# ATtiny.net
KiCad netlist of a schematic drawn in Altium Designer
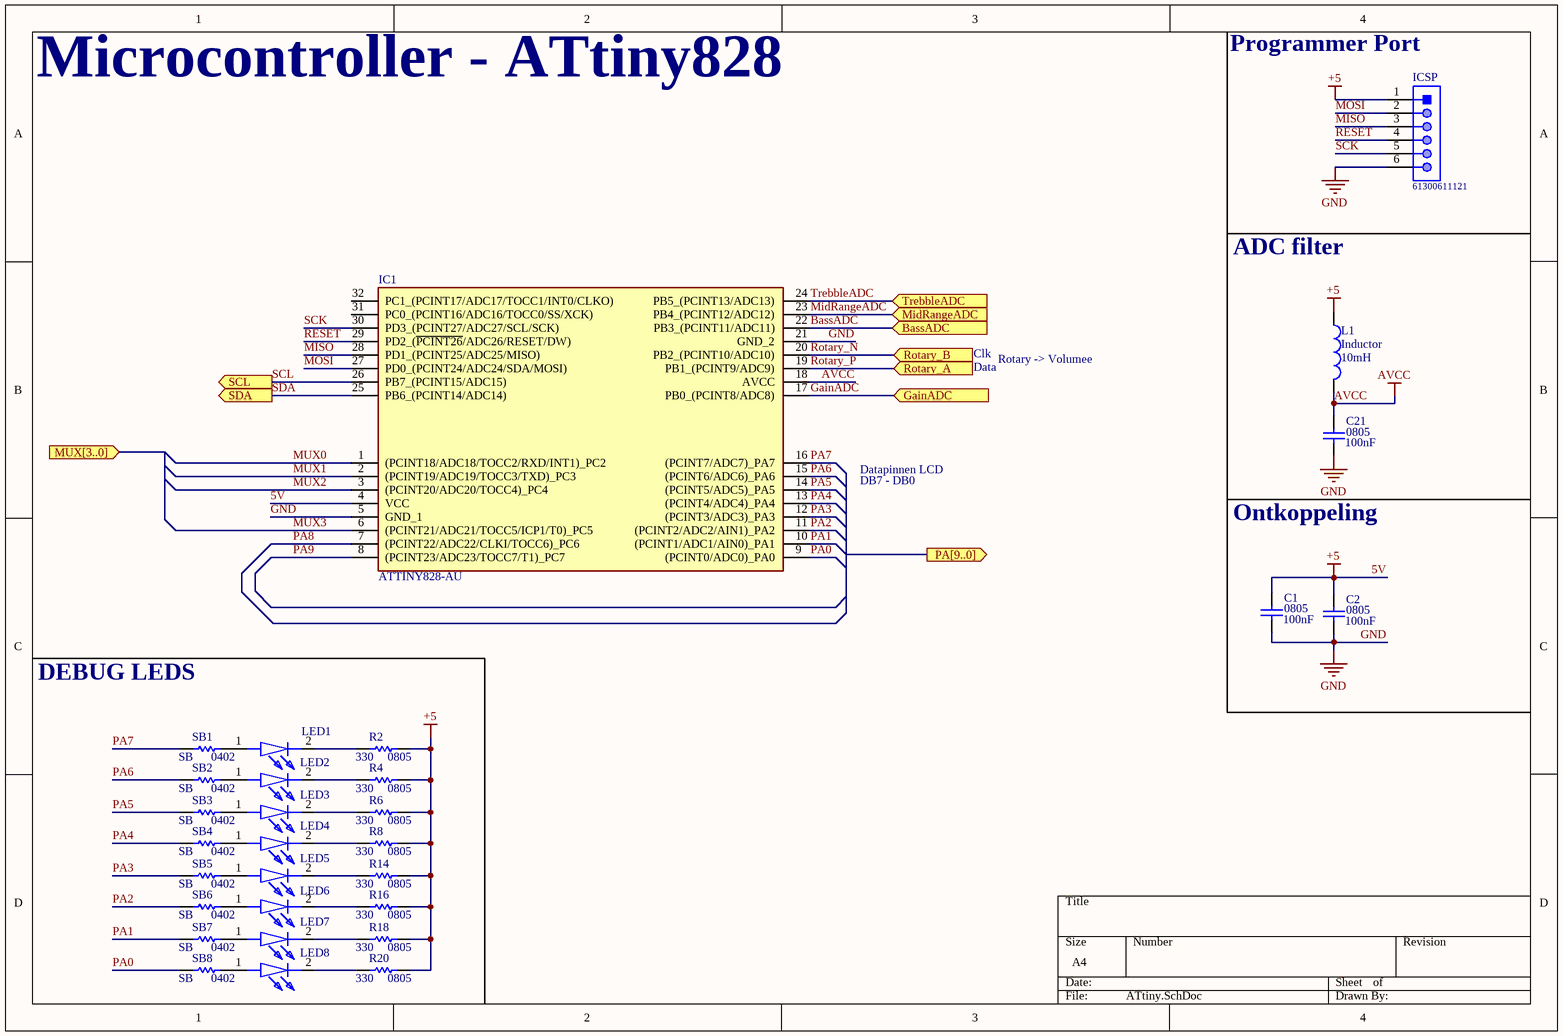
[diagram p0: ATtiny.SchDoc]

(export (version "E")
  (design (tool "Eeschema 10.0.6"))
  (components
    (comp (ref "C1")
      (value "0805")
      (footprint "6-0805_N")
      (description "Capacitor")
      (fields (field (name "ALTIUM_VALUE") "100nF") (field (name "PUBLISHER") "Altium Limited"))
      (libsource (lib "Miscellaneous Devices") (part "Cap"))
    )
    (comp (ref "C2")
      (value "0805")
      (footprint "6-0805_N")
      (description "Capacitor")
      (fields (field (name "ALTIUM_VALUE") "100nF") (field (name "PUBLISHER") "Altium Limited"))
      (libsource (lib "Miscellaneous Devices") (part "Cap"))
    )
    (comp (ref "C21")
      (value "0805")
      (footprint "6-0805_N")
      (description "Capacitor")
      (fields (field (name "ALTIUM_VALUE") "100nF") (field (name "PUBLISHER") "Altium Limited"))
      (libsource (lib "Miscellaneous Devices") (part "Cap"))
    )
    (comp (ref "IC1")
      (value "ATTINY828-AU")
      (footprint "SamacSys:QFP80P900X900X120-32N")
      (description "Integrated Circuit")
      (libsource (lib "SamacSys") (part "ATTINY828-AU"))
    )
    (comp (ref "ICSP")
      (value "61300611121")
      (footprint "61300611121")
      (description "THT Vertical Pin Header WR-PHD, Pitch 2.54 mm, Single Row, 6 pins")
      (fields (field (name "MANUFACTURER") "Wurth Elektronik") (field (name "PUBLISHER") "WurthElektronik"))
      (libsource (lib "Altium Content Vault") (part "WE-CN-1P-M-R6"))
    )
    (comp (ref "L1")
      (value "Inductor")
      (footprint "2220")
      (fields (field (name "ALTIUM_VALUE") "10mH") (field (name "PUBLISHER") "Altium Limited"))
      (libsource (lib "Miscellaneous Devices") (part "Inductor"))
    )
    (comp (ref "LED1")
      (value "ELM70303GD")
      (footprint "SamacSys:ELM70303GD")
      (description "LED")
      (fields (field (name "MOUSER PART NUMBER") "749-ELM70303GD"))
      (libsource (lib "SamacSys") (part "ELM70303GD"))
    )
    (comp (ref "LED2")
      (value "ELM70303GD")
      (footprint "SamacSys:ELM70303GD")
      (description "LED")
      (fields (field (name "MOUSER PART NUMBER") "749-ELM70303GD"))
      (libsource (lib "SamacSys") (part "ELM70303GD"))
    )
    (comp (ref "LED3")
      (value "ELM70303GD")
      (footprint "SamacSys:ELM70303GD")
      (description "LED")
      (fields (field (name "MOUSER PART NUMBER") "749-ELM70303GD"))
      (libsource (lib "SamacSys") (part "ELM70303GD"))
    )
    (comp (ref "LED4")
      (value "ELM70303GD")
      (footprint "SamacSys:ELM70303GD")
      (description "LED")
      (fields (field (name "MOUSER PART NUMBER") "749-ELM70303GD"))
      (libsource (lib "SamacSys") (part "ELM70303GD"))
    )
    (comp (ref "LED5")
      (value "ELM70303GD")
      (footprint "SamacSys:ELM70303GD")
      (description "LED")
      (fields (field (name "MOUSER PART NUMBER") "749-ELM70303GD"))
      (libsource (lib "SamacSys") (part "ELM70303GD"))
    )
    (comp (ref "LED6")
      (value "ELM70303GD")
      (footprint "SamacSys:ELM70303GD")
      (description "LED")
      (fields (field (name "MOUSER PART NUMBER") "749-ELM70303GD"))
      (libsource (lib "SamacSys") (part "ELM70303GD"))
    )
    (comp (ref "LED7")
      (value "ELM70303GD")
      (footprint "SamacSys:ELM70303GD")
      (description "LED")
      (fields (field (name "MOUSER PART NUMBER") "749-ELM70303GD"))
      (libsource (lib "SamacSys") (part "ELM70303GD"))
    )
    (comp (ref "LED8")
      (value "ELM70303GD")
      (footprint "SamacSys:ELM70303GD")
      (description "LED")
      (fields (field (name "MOUSER PART NUMBER") "749-ELM70303GD"))
      (libsource (lib "SamacSys") (part "ELM70303GD"))
    )
    (comp (ref "R2")
      (value "0805")
      (footprint "6-0805_N")
      (description "Resistor")
      (fields (field (name "ALTIUM_VALUE") "330") (field (name "PUBLISHER") "Altium Limited"))
      (libsource (lib "Miscellaneous Devices") (part "Res1"))
    )
    (comp (ref "R4")
      (value "0805")
      (footprint "6-0805_N")
      (description "Resistor")
      (fields (field (name "ALTIUM_VALUE") "330") (field (name "PUBLISHER") "Altium Limited"))
      (libsource (lib "Miscellaneous Devices") (part "Res1"))
    )
    (comp (ref "R6")
      (value "0805")
      (footprint "6-0805_N")
      (description "Resistor")
      (fields (field (name "ALTIUM_VALUE") "330") (field (name "PUBLISHER") "Altium Limited"))
      (libsource (lib "Miscellaneous Devices") (part "Res1"))
    )
    (comp (ref "R8")
      (value "0805")
      (footprint "6-0805_N")
      (description "Resistor")
      (fields (field (name "ALTIUM_VALUE") "330") (field (name "PUBLISHER") "Altium Limited"))
      (libsource (lib "Miscellaneous Devices") (part "Res1"))
    )
    (comp (ref "R14")
      (value "0805")
      (footprint "6-0805_N")
      (description "Resistor")
      (fields (field (name "ALTIUM_VALUE") "330") (field (name "PUBLISHER") "Altium Limited"))
      (libsource (lib "Miscellaneous Devices") (part "Res1"))
    )
    (comp (ref "R16")
      (value "0805")
      (footprint "6-0805_N")
      (description "Resistor")
      (fields (field (name "ALTIUM_VALUE") "330") (field (name "PUBLISHER") "Altium Limited"))
      (libsource (lib "Miscellaneous Devices") (part "Res1"))
    )
    (comp (ref "R18")
      (value "0805")
      (footprint "6-0805_N")
      (description "Resistor")
      (fields (field (name "ALTIUM_VALUE") "330") (field (name "PUBLISHER") "Altium Limited"))
      (libsource (lib "Miscellaneous Devices") (part "Res1"))
    )
    (comp (ref "R20")
      (value "0805")
      (footprint "6-0805_N")
      (description "Resistor")
      (fields (field (name "ALTIUM_VALUE") "330") (field (name "PUBLISHER") "Altium Limited"))
      (libsource (lib "Miscellaneous Devices") (part "Res1"))
    )
    (comp (ref "SB1")
      (value "0402")
      (footprint "0402")
      (description "Resistor")
      (fields (field (name "ALTIUM_VALUE") "SB") (field (name "PUBLISHER") "Altium Limited"))
      (libsource (lib "Miscellaneous Devices") (part "Res1"))
    )
    (comp (ref "SB2")
      (value "0402")
      (footprint "0402")
      (description "Resistor")
      (fields (field (name "ALTIUM_VALUE") "SB") (field (name "PUBLISHER") "Altium Limited"))
      (libsource (lib "Miscellaneous Devices") (part "Res1"))
    )
    (comp (ref "SB3")
      (value "0402")
      (footprint "0402")
      (description "Resistor")
      (fields (field (name "ALTIUM_VALUE") "SB") (field (name "PUBLISHER") "Altium Limited"))
      (libsource (lib "Miscellaneous Devices") (part "Res1"))
    )
    (comp (ref "SB4")
      (value "0402")
      (footprint "0402")
      (description "Resistor")
      (fields (field (name "ALTIUM_VALUE") "SB") (field (name "PUBLISHER") "Altium Limited"))
      (libsource (lib "Miscellaneous Devices") (part "Res1"))
    )
    (comp (ref "SB5")
      (value "0402")
      (footprint "0402")
      (description "Resistor")
      (fields (field (name "ALTIUM_VALUE") "SB") (field (name "PUBLISHER") "Altium Limited"))
      (libsource (lib "Miscellaneous Devices") (part "Res1"))
    )
    (comp (ref "SB6")
      (value "0402")
      (footprint "0402")
      (description "Resistor")
      (fields (field (name "ALTIUM_VALUE") "SB") (field (name "PUBLISHER") "Altium Limited"))
      (libsource (lib "Miscellaneous Devices") (part "Res1"))
    )
    (comp (ref "SB7")
      (value "0402")
      (footprint "0402")
      (description "Resistor")
      (fields (field (name "ALTIUM_VALUE") "SB") (field (name "PUBLISHER") "Altium Limited"))
      (libsource (lib "Miscellaneous Devices") (part "Res1"))
    )
    (comp (ref "SB8")
      (value "0402")
      (footprint "0402")
      (description "Resistor")
      (fields (field (name "ALTIUM_VALUE") "SB") (field (name "PUBLISHER") "Altium Limited"))
      (libsource (lib "Miscellaneous Devices") (part "Res1"))
    )
  )
  (nets
    (net (code "1") (name "+5") (class "Default")
      (node (ref "C1") (pin "1") (pinfunction "1_1") (pintype "passive"))
      (node (ref "C2") (pin "1") (pinfunction "1_1") (pintype "passive"))
      (node (ref "IC1") (pin "4") (pinfunction "VCC_4") (pintype "passive"))
      (node (ref "ICSP") (pin "1") (pinfunction "1_1") (pintype "passive"))
      (node (ref "L1") (pin "1") (pinfunction "1_1") (pintype "passive"))
      (node (ref "R14") (pin "1") (pinfunction "1_1") (pintype "passive"))
      (node (ref "R16") (pin "1") (pinfunction "1_1") (pintype "passive"))
      (node (ref "R18") (pin "1") (pinfunction "1_1") (pintype "passive"))
      (node (ref "R2") (pin "1") (pinfunction "1_1") (pintype "passive"))
      (node (ref "R20") (pin "1") (pinfunction "1_1") (pintype "passive"))
      (node (ref "R4") (pin "1") (pinfunction "1_1") (pintype "passive"))
      (node (ref "R6") (pin "1") (pinfunction "1_1") (pintype "passive"))
      (node (ref "R8") (pin "1") (pinfunction "1_1") (pintype "passive"))
    )
    (net (code "2") (name "/BassADC") (class "Default")
      (node (ref "IC1") (pin "22") (pinfunction "PB3_(PCINT11/ADC11)_22") (pintype "passive"))
    )
    (net (code "3") (name "/GainADC") (class "Default")
      (node (ref "IC1") (pin "17") (pinfunction "PB0_(PCINT8/ADC8)_17") (pintype "passive"))
    )
    (net (code "4") (name "/MISO") (class "Default")
      (node (ref "IC1") (pin "28") (pinfunction "PD1_(PCINT25/ADC25/MISO)_28") (pintype "passive"))
      (node (ref "ICSP") (pin "3") (pinfunction "3_3") (pintype "passive"))
    )
    (net (code "5") (name "/MOSI") (class "Default")
      (node (ref "IC1") (pin "27") (pinfunction "PD0_(PCINT24/ADC24/SDA/MOSI)_27") (pintype "passive"))
      (node (ref "ICSP") (pin "2") (pinfunction "2_2") (pintype "passive"))
    )
    (net (code "6") (name "/MUX0") (class "Default")
      (node (ref "IC1") (pin "1") (pinfunction "(PCINT18/ADC18/TOCC2/RXD/INT1)_PC2_1") (pintype "passive"))
    )
    (net (code "7") (name "/MUX1") (class "Default")
      (node (ref "IC1") (pin "2") (pinfunction "(PCINT19/ADC19/TOCC3/TXD)_PC3_2") (pintype "passive"))
    )
    (net (code "8") (name "/MUX2") (class "Default")
      (node (ref "IC1") (pin "3") (pinfunction "(PCINT20/ADC20/TOCC4)_PC4_3") (pintype "passive"))
    )
    (net (code "9") (name "/MUX3") (class "Default")
      (node (ref "IC1") (pin "6") (pinfunction "(PCINT21/ADC21/TOCC5/ICP1/T0)_PC5_6") (pintype "passive"))
    )
    (net (code "11") (name "/MidRangeADC") (class "Default")
      (node (ref "IC1") (pin "23") (pinfunction "PB4_(PCINT12/ADC12)_23") (pintype "passive"))
    )
    (net (code "12") (name "/PA0") (class "Default")
      (node (ref "IC1") (pin "9") (pinfunction "(PCINT0/ADC0)_PA0_9") (pintype "passive"))
      (node (ref "SB8") (pin "2") (pinfunction "2_2") (pintype "passive"))
    )
    (net (code "13") (name "/PA1") (class "Default")
      (node (ref "IC1") (pin "10") (pinfunction "(PCINT1/ADC1/AIN0)_PA1_10") (pintype "passive"))
      (node (ref "SB7") (pin "2") (pinfunction "2_2") (pintype "passive"))
    )
    (net (code "14") (name "/PA2") (class "Default")
      (node (ref "IC1") (pin "11") (pinfunction "(PCINT2/ADC2/AIN1)_PA2_11") (pintype "passive"))
      (node (ref "SB6") (pin "2") (pinfunction "2_2") (pintype "passive"))
    )
    (net (code "15") (name "/PA3") (class "Default")
      (node (ref "IC1") (pin "12") (pinfunction "(PCINT3/ADC3)_PA3_12") (pintype "passive"))
      (node (ref "SB5") (pin "2") (pinfunction "2_2") (pintype "passive"))
    )
    (net (code "16") (name "/PA4") (class "Default")
      (node (ref "IC1") (pin "13") (pinfunction "(PCINT4/ADC4)_PA4_13") (pintype "passive"))
      (node (ref "SB4") (pin "2") (pinfunction "2_2") (pintype "passive"))
    )
    (net (code "17") (name "/PA5") (class "Default")
      (node (ref "IC1") (pin "14") (pinfunction "(PCINT5/ADC5)_PA5_14") (pintype "passive"))
      (node (ref "SB3") (pin "2") (pinfunction "2_2") (pintype "passive"))
    )
    (net (code "18") (name "/PA6") (class "Default")
      (node (ref "IC1") (pin "15") (pinfunction "(PCINT6/ADC6)_PA6_15") (pintype "passive"))
      (node (ref "SB2") (pin "2") (pinfunction "2_2") (pintype "passive"))
    )
    (net (code "19") (name "/PA7") (class "Default")
      (node (ref "IC1") (pin "16") (pinfunction "(PCINT7/ADC7)_PA7_16") (pintype "passive"))
      (node (ref "SB1") (pin "2") (pinfunction "2_2") (pintype "passive"))
    )
    (net (code "20") (name "/PA8") (class "Default")
      (node (ref "IC1") (pin "7") (pinfunction "(PCINT22/ADC22/CLKI/TOCC6)_PC6_7") (pintype "passive"))
    )
    (net (code "21") (name "/PA9") (class "Default")
      (node (ref "IC1") (pin "8") (pinfunction "(PCINT23/ADC23/TOCC7/T1)_PC7_8") (pintype "passive"))
    )
    (net (code "23") (name "/RESET") (class "Default")
      (node (ref "IC1") (pin "29") (pinfunction "PD2_(~{PCINT26}/ADC26/RESET/DW)_29") (pintype "passive"))
      (node (ref "ICSP") (pin "4") (pinfunction "4_4") (pintype "passive"))
    )
    (net (code "24") (name "/Rotary_N") (class "Default")
      (node (ref "IC1") (pin "20") (pinfunction "PB2_(PCINT10/ADC10)_20") (pintype "passive"))
    )
    (net (code "25") (name "/Rotary_P") (class "Default")
      (node (ref "IC1") (pin "19") (pinfunction "PB1_(PCINT9/ADC9)_19") (pintype "passive"))
    )
    (net (code "26") (name "/SCK") (class "Default")
      (node (ref "IC1") (pin "30") (pinfunction "PD3_(PCINT27/ADC27/SCL/SCK)_30") (pintype "passive"))
      (node (ref "ICSP") (pin "5") (pinfunction "5_5") (pintype "passive"))
    )
    (net (code "27") (name "/SCL") (class "Default")
      (node (ref "IC1") (pin "26") (pinfunction "PB7_(PCINT15/ADC15)_26") (pintype "passive"))
    )
    (net (code "28") (name "/SDA") (class "Default")
      (node (ref "IC1") (pin "25") (pinfunction "PB6_(PCINT14/ADC14)_25") (pintype "passive"))
    )
    (net (code "29") (name "/TrebbleADC") (class "Default")
      (node (ref "IC1") (pin "24") (pinfunction "PB5_(PCINT13/ADC13)_24") (pintype "passive"))
    )
    (net (code "30") (name "AVCC") (class "Default")
      (node (ref "C21") (pin "1") (pinfunction "1_1") (pintype "passive"))
      (node (ref "IC1") (pin "18") (pinfunction "AVCC_18") (pintype "passive"))
      (node (ref "L1") (pin "2") (pinfunction "2_2") (pintype "passive"))
    )
    (net (code "31") (name "GND") (class "Default")
      (node (ref "C1") (pin "2") (pinfunction "2_2") (pintype "passive"))
      (node (ref "C2") (pin "2") (pinfunction "2_2") (pintype "passive"))
      (node (ref "C21") (pin "2") (pinfunction "2_2") (pintype "passive"))
      (node (ref "IC1") (pin "21") (pinfunction "GND_2_21") (pintype "passive"))
      (node (ref "IC1") (pin "5") (pinfunction "GND_1_5") (pintype "passive"))
      (node (ref "ICSP") (pin "6") (pinfunction "6_6") (pintype "passive"))
    )
    (net (code "32") (name "Net-(LED1-A)") (class "Default")
      (node (ref "LED1") (pin "1") (pinfunction "A_1") (pintype "passive"))
      (node (ref "SB1") (pin "1") (pinfunction "1_1") (pintype "passive"))
    )
    (net (code "33") (name "Net-(LED1-K)") (class "Default")
      (node (ref "LED1") (pin "2") (pinfunction "K_2") (pintype "passive"))
      (node (ref "R2") (pin "2") (pinfunction "2_2") (pintype "passive"))
    )
    (net (code "34") (name "Net-(LED2-A)") (class "Default")
      (node (ref "LED2") (pin "1") (pinfunction "A_1") (pintype "passive"))
      (node (ref "SB2") (pin "1") (pinfunction "1_1") (pintype "passive"))
    )
    (net (code "35") (name "Net-(LED2-K)") (class "Default")
      (node (ref "LED2") (pin "2") (pinfunction "K_2") (pintype "passive"))
      (node (ref "R4") (pin "2") (pinfunction "2_2") (pintype "passive"))
    )
    (net (code "36") (name "Net-(LED3-A)") (class "Default")
      (node (ref "LED3") (pin "1") (pinfunction "A_1") (pintype "passive"))
      (node (ref "SB3") (pin "1") (pinfunction "1_1") (pintype "passive"))
    )
    (net (code "37") (name "Net-(LED3-K)") (class "Default")
      (node (ref "LED3") (pin "2") (pinfunction "K_2") (pintype "passive"))
      (node (ref "R6") (pin "2") (pinfunction "2_2") (pintype "passive"))
    )
    (net (code "38") (name "Net-(LED4-A)") (class "Default")
      (node (ref "LED4") (pin "1") (pinfunction "A_1") (pintype "passive"))
      (node (ref "SB4") (pin "1") (pinfunction "1_1") (pintype "passive"))
    )
    (net (code "39") (name "Net-(LED4-K)") (class "Default")
      (node (ref "LED4") (pin "2") (pinfunction "K_2") (pintype "passive"))
      (node (ref "R8") (pin "2") (pinfunction "2_2") (pintype "passive"))
    )
    (net (code "40") (name "Net-(LED5-A)") (class "Default")
      (node (ref "LED5") (pin "1") (pinfunction "A_1") (pintype "passive"))
      (node (ref "SB5") (pin "1") (pinfunction "1_1") (pintype "passive"))
    )
    (net (code "41") (name "Net-(LED5-K)") (class "Default")
      (node (ref "LED5") (pin "2") (pinfunction "K_2") (pintype "passive"))
      (node (ref "R14") (pin "2") (pinfunction "2_2") (pintype "passive"))
    )
    (net (code "42") (name "Net-(LED6-A)") (class "Default")
      (node (ref "LED6") (pin "1") (pinfunction "A_1") (pintype "passive"))
      (node (ref "SB6") (pin "1") (pinfunction "1_1") (pintype "passive"))
    )
    (net (code "43") (name "Net-(LED6-K)") (class "Default")
      (node (ref "LED6") (pin "2") (pinfunction "K_2") (pintype "passive"))
      (node (ref "R16") (pin "2") (pinfunction "2_2") (pintype "passive"))
    )
    (net (code "44") (name "Net-(LED7-A)") (class "Default")
      (node (ref "LED7") (pin "1") (pinfunction "A_1") (pintype "passive"))
      (node (ref "SB7") (pin "1") (pinfunction "1_1") (pintype "passive"))
    )
    (net (code "45") (name "Net-(LED7-K)") (class "Default")
      (node (ref "LED7") (pin "2") (pinfunction "K_2") (pintype "passive"))
      (node (ref "R18") (pin "2") (pinfunction "2_2") (pintype "passive"))
    )
    (net (code "46") (name "Net-(LED8-A)") (class "Default")
      (node (ref "LED8") (pin "1") (pinfunction "A_1") (pintype "passive"))
      (node (ref "SB8") (pin "1") (pinfunction "1_1") (pintype "passive"))
    )
    (net (code "47") (name "Net-(LED8-K)") (class "Default")
      (node (ref "LED8") (pin "2") (pinfunction "K_2") (pintype "passive"))
      (node (ref "R20") (pin "2") (pinfunction "2_2") (pintype "passive"))
    )
    (net (code "48") (name "unconnected-(IC1-PC0_(PCINT16{slash}ADC16{slash}TOCC0{slash}SS{slash}XCK)-Pad31)") (class "Default")
      (node (ref "IC1") (pin "31") (pinfunction "PC0_(PCINT16/ADC16/TOCC0/SS/XCK)_31") (pintype "passive"))
    )
    (net (code "49") (name "unconnected-(IC1-PC1_(PCINT17{slash}ADC17{slash}TOCC1{slash}INT0{slash}CLKO)-Pad32)") (class "Default")
      (node (ref "IC1") (pin "32") (pinfunction "PC1_(PCINT17/ADC17/TOCC1/INT0/CLKO)_32") (pintype "passive"))
    )
  )
)
